# Parking_Sensor_USB_-v18.net
KiCad netlist of a schematic drawn in EAGLE
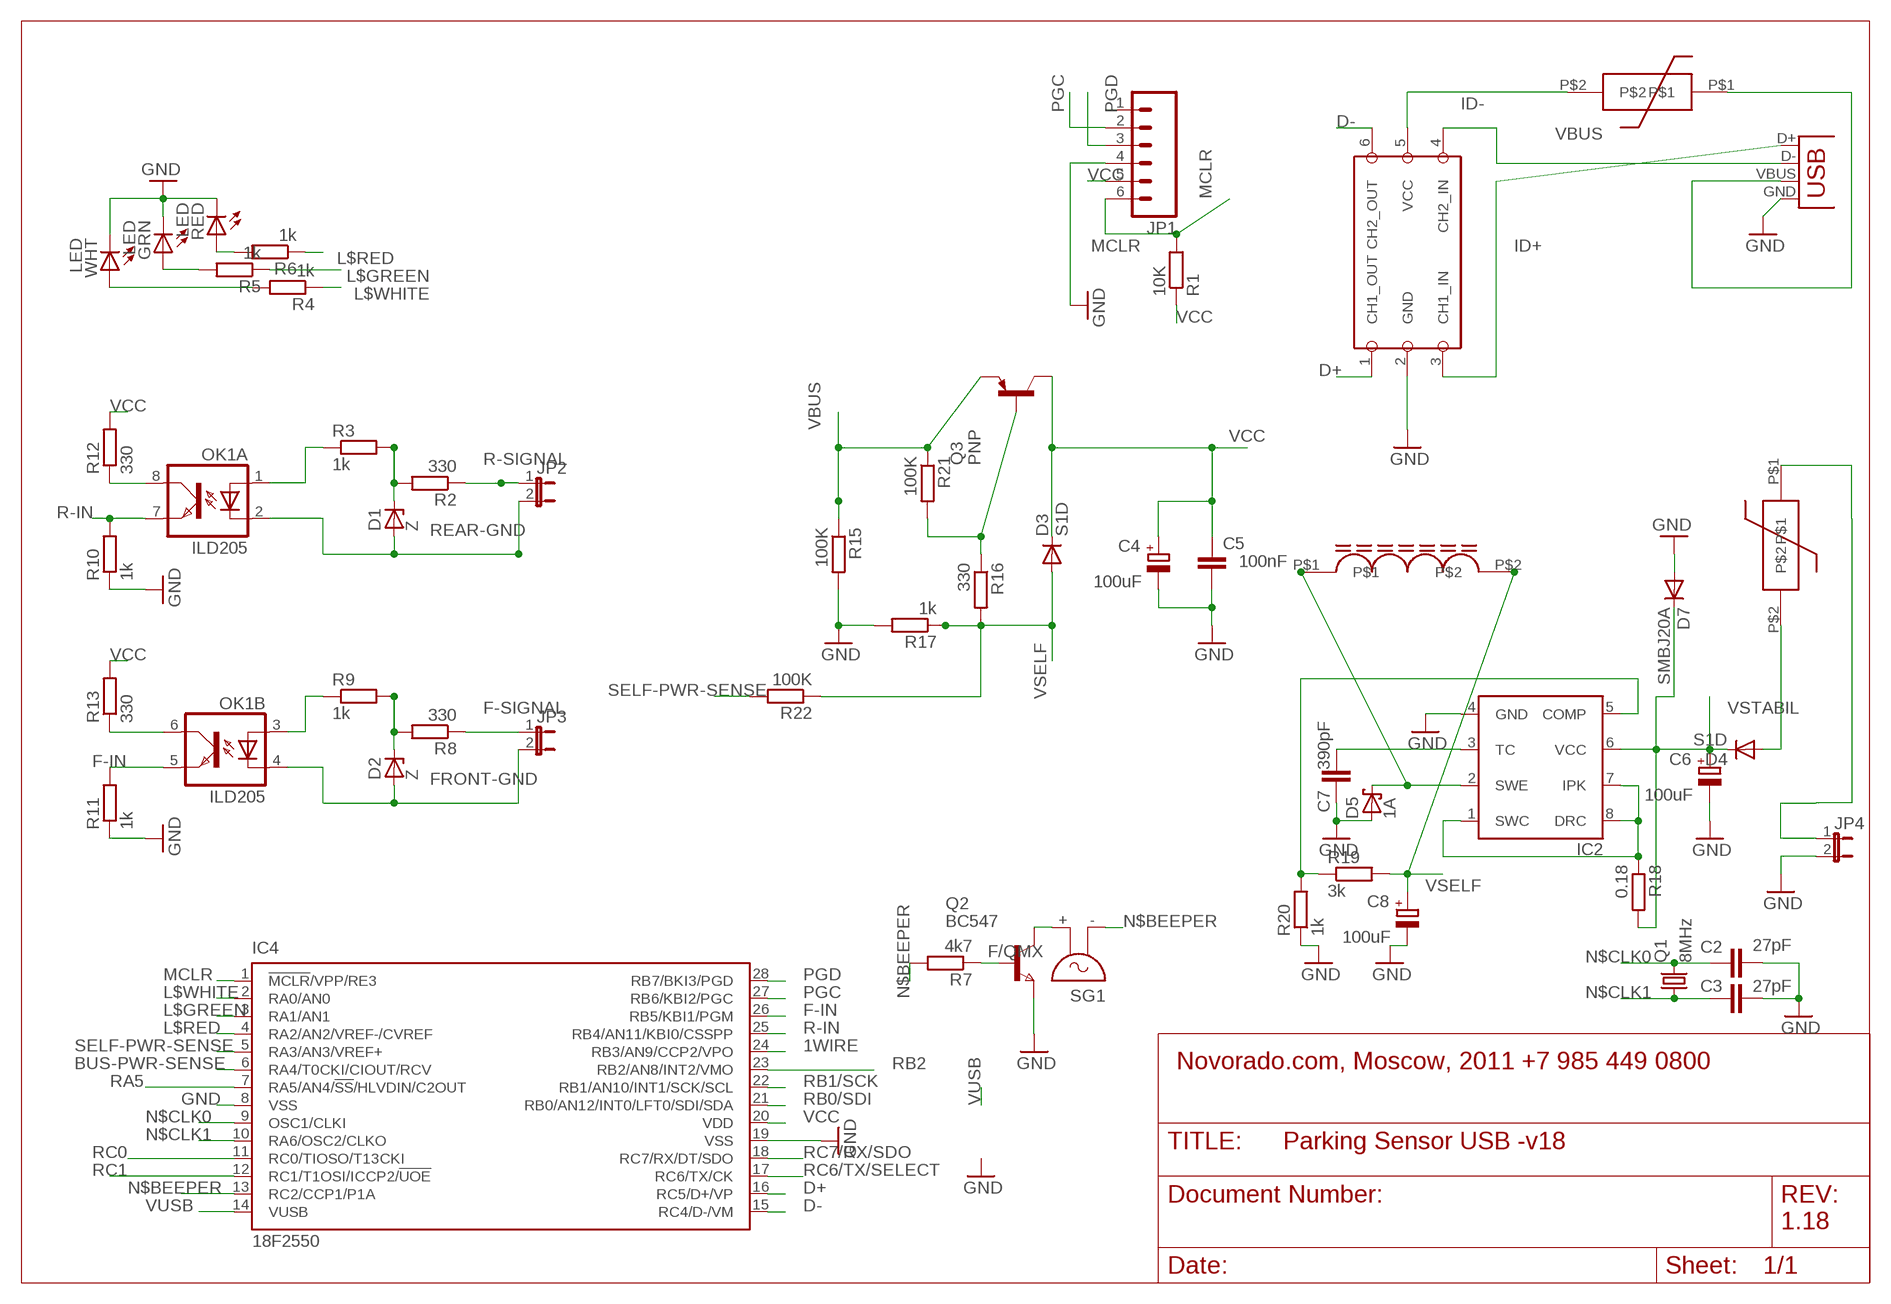
[diagram p0: schematic, sheet 1]

(export (version "E")
  (design (tool "Eeschema 10.0.6"))
  (components
    (comp (ref "C2")
      (value "27pF")
      (footprint "eagle-import:C1206")
      (libsource (lib "eagle-import") (part "C-EUC1206"))
    )
    (comp (ref "C3")
      (value "27pF")
      (footprint "eagle-import:C1206")
      (libsource (lib "eagle-import") (part "C-EUC1206"))
    )
    (comp (ref "C4")
      (value "100uF")
      (footprint "eagle-import:153CLV-0505")
      (libsource (lib "eagle-import") (part "CPOL-EU153CLV-0505"))
    )
    (comp (ref "C5")
      (value "100nF")
      (footprint "eagle-import:C0603")
      (libsource (lib "eagle-import") (part "C-EUC0603"))
    )
    (comp (ref "C6")
      (value "100uF")
      (footprint "eagle-import:153CLV-0505")
      (libsource (lib "eagle-import") (part "CPOL-EU153CLV-0505"))
    )
    (comp (ref "C7")
      (value "390pF")
      (footprint "eagle-import:C0805")
      (libsource (lib "eagle-import") (part "C-EUC0805"))
    )
    (comp (ref "C8")
      (value "100uF")
      (footprint "eagle-import:153CLV-0505")
      (libsource (lib "eagle-import") (part "CPOL-EU153CLV-0505"))
    )
    (comp (ref "D1")
      (value "Z")
      (footprint "eagle-import:SOT23")
      (libsource (lib "eagle-import") (part "ZENER-DIODESOT23"))
    )
    (comp (ref "D2")
      (value "Z")
      (footprint "eagle-import:SOT23")
      (libsource (lib "eagle-import") (part "ZENER-DIODESOT23"))
    )
    (comp (ref "D3")
      (value "S1D")
      (footprint "eagle-import:DO214AC")
      (libsource (lib "eagle-import") (part "DIODE-DO214AC"))
    )
    (comp (ref "D4")
      (value "S1D")
      (footprint "eagle-import:DO-214AC")
      (libsource (lib "eagle-import") (part "DIODE-DO-214AC"))
    )
    (comp (ref "D5")
      (value "1A")
      (footprint "eagle-import:SMB")
      (libsource (lib "eagle-import") (part "MBRS130LT3"))
    )
    (comp (ref "D7")
      (value "SMBJ20A")
      (footprint "eagle-import:DO214AA")
      (libsource (lib "eagle-import") (part "DIODE-DO214AA"))
    )
    (comp (ref "GRN")
      (value "LED")
      (footprint "eagle-import:CHIPLED_0805")
      (libsource (lib "eagle-import") (part "LEDCHIPLED_0805"))
    )
    (comp (ref "IC2")
      (value "MC34063AD")
      (footprint "eagle-import:SO08")
      (libsource (lib "eagle-import") (part "MC34063AD"))
    )
    (comp (ref "IC4")
      (value "18F2550")
      (footprint "eagle-import:SO28W")
      (fields
        (field (name "MF") "MICROCHIP")
        (field (name "MPN") "PIC18F2550-I/SO")
        (field (name "MPN_1") "PIC18F2550-I/SO")
        (field (name "OC_FARNELL") "9321268")
        (field (name "OC_NEWARK") "73K1297")
      )
      (libsource (lib "eagle-import") (part "PIC18F2_28W550"))
    )
    (comp (ref "JP1")
      (value "M06SMD")
      (footprint "eagle-import:1X06-SMD")
      (libsource (lib "eagle-import") (part "M06SMD"))
    )
    (comp (ref "JP2")
      (value "JP1E")
      (footprint "eagle-import:JP1")
      (libsource (lib "eagle-import") (part "JP1E"))
    )
    (comp (ref "JP3")
      (value "JP1E")
      (footprint "eagle-import:JP1")
      (libsource (lib "eagle-import") (part "JP1E"))
    )
    (comp (ref "JP4")
      (value "JP1E")
      (footprint "eagle-import:JP1")
      (libsource (lib "eagle-import") (part "JP1E"))
    )
    (comp (ref "OK1")
      (value "ILD205")
      (footprint "eagle-import:SOIC08")
      (fields (field (name "MF") "VISHAY/TELEFUNKEN") (field (name "MPN") "ILD205T"))
      (libsource (lib "eagle-import") (part "ILD205"))
    )
    (comp (ref "Q1")
      (value "8MHz")
      (footprint "eagle-import:HC49UP")
      (fields (field (name "OC_FARNELL") "unknown"))
      (libsource (lib "eagle-import") (part "CRYSTALHC49UP"))
    )
    (comp (ref "Q2")
      (value "BC547")
      (footprint "eagle-import:SOT-23")
      (fields (field (name "MPN") "DSS20201L-7"))
      (libsource (lib "eagle-import") (part "NPNSOT23"))
    )
    (comp (ref "Q3")
      (value "PNP")
      (footprint "eagle-import:SOT23-BEC")
      (libsource (lib "eagle-import") (part "BC807SMD-40"))
    )
    (comp (ref "R1")
      (value "10K")
      (footprint "eagle-import:M1206")
      (libsource (lib "eagle-import") (part "R-EU_M1206"))
    )
    (comp (ref "R2")
      (value "330")
      (footprint "eagle-import:M1206")
      (libsource (lib "eagle-import") (part "resistor_R-EU_M1206"))
    )
    (comp (ref "R3")
      (value "1k")
      (footprint "eagle-import:M1206")
      (libsource (lib "eagle-import") (part "resistor_R-EU_M1206"))
    )
    (comp (ref "R4")
      (value "1k")
      (footprint "eagle-import:M1206")
      (libsource (lib "eagle-import") (part "resistor_R-EU_M1206"))
    )
    (comp (ref "R5")
      (value "1k")
      (footprint "eagle-import:M1206")
      (libsource (lib "eagle-import") (part "resistor_R-EU_M1206"))
    )
    (comp (ref "R6")
      (value "1k")
      (footprint "eagle-import:M1206")
      (libsource (lib "eagle-import") (part "resistor_R-EU_M1206"))
    )
    (comp (ref "R7")
      (value "4k7")
      (footprint "eagle-import:M1206")
      (libsource (lib "eagle-import") (part "R-EU_M1206"))
    )
    (comp (ref "R8")
      (value "330")
      (footprint "eagle-import:M1206")
      (libsource (lib "eagle-import") (part "resistor_R-EU_M1206"))
    )
    (comp (ref "R9")
      (value "1k")
      (footprint "eagle-import:M1206")
      (libsource (lib "eagle-import") (part "resistor_R-EU_M1206"))
    )
    (comp (ref "R10")
      (value "1k")
      (footprint "eagle-import:M1206")
      (libsource (lib "eagle-import") (part "resistor_R-EU_M1206"))
    )
    (comp (ref "R11")
      (value "1k")
      (footprint "eagle-import:M1206")
      (libsource (lib "eagle-import") (part "resistor_R-EU_M1206"))
    )
    (comp (ref "R12")
      (value "330")
      (footprint "eagle-import:M1206")
      (libsource (lib "eagle-import") (part "resistor_R-EU_M1206"))
    )
    (comp (ref "R13")
      (value "330")
      (footprint "eagle-import:M1206")
      (libsource (lib "eagle-import") (part "resistor_R-EU_M1206"))
    )
    (comp (ref "R15")
      (value "100K")
      (footprint "eagle-import:M1206")
      (libsource (lib "eagle-import") (part "R-EU_M1206"))
    )
    (comp (ref "R16")
      (value "330")
      (footprint "eagle-import:M1206")
      (libsource (lib "eagle-import") (part "R-EU_M1206"))
    )
    (comp (ref "R17")
      (value "1k")
      (footprint "eagle-import:M1206")
      (libsource (lib "eagle-import") (part "R-EU_M1206"))
    )
    (comp (ref "R18")
      (value "0.18")
      (footprint "eagle-import:0204_7")
      (libsource (lib "eagle-import") (part "R-EU_0204/7"))
    )
    (comp (ref "R19")
      (value "3k")
      (footprint "eagle-import:M1206")
      (libsource (lib "eagle-import") (part "resistor_R-EU_M1206"))
    )
    (comp (ref "R20")
      (value "1k")
      (footprint "eagle-import:M1206")
      (libsource (lib "eagle-import") (part "resistor_R-EU_M1206"))
    )
    (comp (ref "R21")
      (value "100K")
      (footprint "eagle-import:M1206")
      (libsource (lib "eagle-import") (part "R-EU_M1206"))
    )
    (comp (ref "R22")
      (value "100K")
      (footprint "eagle-import:M1206")
      (libsource (lib "eagle-import") (part "R-EU_M1206"))
    )
    (comp (ref "RED")
      (value "LED")
      (footprint "eagle-import:CHIPLED_0805")
      (libsource (lib "eagle-import") (part "LEDCHIPLED_0805"))
    )
    (comp (ref "SG1")
      (value "F/QMX")
      (footprint "eagle-import:F_QMX")
      (libsource (lib "eagle-import") (part "F/QMX"))
    )
    (comp (ref "U$1")
      (value "EMI")
      (footprint "eagle-import:SOT23-DBV")
      (libsource (lib "eagle-import") (part "TPD2S017DBVR"))
    )
    (comp (ref "U$2")
      (value "MF-SM050")
      (footprint "eagle-import:SMD2029")
      (libsource (lib "eagle-import") (part "MF-SM050"))
    )
    (comp (ref "U$3")
      (value "MF-SM050")
      (footprint "eagle-import:SMD2029")
      (libsource (lib "eagle-import") (part "MF-SM050"))
    )
    (comp (ref "U$5")
      (value "SDR0302")
      (footprint "eagle-import:SDR0302")
      (libsource (lib "eagle-import") (part "SDR0302"))
    )
    (comp (ref "WHT")
      (value "LED")
      (footprint "eagle-import:CHIP-LED0805")
      (libsource (lib "eagle-import") (part "LEDCHIP-LED0805"))
    )
    (comp (ref "X2")
      (value "USBSMD")
      (footprint "eagle-import:USB-MINIB")
      (libsource (lib "eagle-import") (part "USBSMD"))
    )
  )
  (nets
    (net (code "1") (name "/1WIRE") (class "Default")
      (node (ref "IC4") (pin "24") (pinfunction "RB3/AN9/CCP2/VPO_24") (pintype "bidirectional"))
    )
    (net (code "2") (name "/BUS-PWR-SENSE") (class "Default")
      (node (ref "IC4") (pin "6") (pinfunction "RA4/T0CKI/CIOUT/RCV_6") (pintype "bidirectional"))
    )
    (net (code "3") (name "/D+") (class "Default")
      (node (ref "IC4") (pin "16") (pinfunction "RC5/D+/VP_16") (pintype "bidirectional"))
      (node (ref "U$1") (pin "1") (pinfunction "CH1_OUT_1") (pintype "bidirectional"))
    )
    (net (code "4") (name "/D-") (class "Default")
      (node (ref "IC4") (pin "15") (pinfunction "RC4/D-/VM_15") (pintype "bidirectional"))
      (node (ref "U$1") (pin "6") (pinfunction "CH2_OUT_6") (pintype "bidirectional"))
    )
    (net (code "5") (name "/F-IN") (class "Default")
      (node (ref "IC4") (pin "26") (pinfunction "RB5/KBI1/PGM_26") (pintype "bidirectional"))
      (node (ref "OK1") (pin "5") (pinfunction "EMIT_5") (pintype "passive"))
      (node (ref "R11") (pin "2") (pinfunction "2_2") (pintype "passive"))
    )
    (net (code "6") (name "/F-SIGNAL") (class "Default")
      (node (ref "JP3") (pin "1") (pinfunction "1_1") (pintype "passive"))
      (node (ref "R8") (pin "1") (pinfunction "1_1") (pintype "passive"))
    )
    (net (code "7") (name "/FRONT-GND") (class "Default")
      (node (ref "D2") (pin "1") (pinfunction "A_1") (pintype "passive"))
      (node (ref "JP3") (pin "2") (pinfunction "2_2") (pintype "passive"))
      (node (ref "OK1") (pin "4") (pinfunction "C_4") (pintype "passive"))
    )
    (net (code "8") (name "/ID+") (class "Default")
      (node (ref "U$1") (pin "3") (pinfunction "CH1_IN_3") (pintype "bidirectional"))
      (node (ref "X2") (pin "D+") (pinfunction "D+_D+") (pintype "bidirectional"))
    )
    (net (code "9") (name "/ID-") (class "Default")
      (node (ref "U$1") (pin "4") (pinfunction "CH2_IN_4") (pintype "bidirectional"))
      (node (ref "X2") (pin "D-") (pinfunction "D-_D-") (pintype "bidirectional"))
    )
    (net (code "10") (name "/L$GREEN") (class "Default")
      (node (ref "IC4") (pin "3") (pinfunction "RA1/AN1_3") (pintype "bidirectional"))
      (node (ref "R5") (pin "1") (pinfunction "1_1") (pintype "passive"))
    )
    (net (code "11") (name "/L$RED") (class "Default")
      (node (ref "IC4") (pin "4") (pinfunction "RA2/AN2/VREF-/CVREF_4") (pintype "bidirectional"))
      (node (ref "R6") (pin "1") (pinfunction "1_1") (pintype "passive"))
    )
    (net (code "12") (name "/L$WHITE") (class "Default")
      (node (ref "IC4") (pin "2") (pinfunction "RA0/AN0_2") (pintype "bidirectional"))
      (node (ref "R4") (pin "1") (pinfunction "1_1") (pintype "passive"))
    )
    (net (code "13") (name "/MCLR") (class "Default")
      (node (ref "IC4") (pin "1") (pinfunction "~{MCLR}/VPP/RE3_1") (pintype "input"))
      (node (ref "JP1") (pin "6") (pinfunction "6_6") (pintype "passive"))
      (node (ref "R1") (pin "2") (pinfunction "2_2") (pintype "passive"))
    )
    (net (code "14") (name "/N$BEEPER") (class "Default")
      (node (ref "IC4") (pin "13") (pinfunction "RC2/CCP1/P1A_13") (pintype "bidirectional"))
      (node (ref "R7") (pin "2") (pinfunction "2_2") (pintype "passive"))
      (node (ref "SG1") (pin "-") (pinfunction "1_-") (pintype "passive"))
    )
    (net (code "15") (name "/N$CLK0") (class "Default")
      (node (ref "C2") (pin "1") (pinfunction "1_1") (pintype "passive"))
      (node (ref "IC4") (pin "9") (pinfunction "OSC1/CLKI_9") (pintype "input"))
      (node (ref "Q1") (pin "2") (pinfunction "2_2") (pintype "passive"))
    )
    (net (code "16") (name "/N$CLK1") (class "Default")
      (node (ref "C3") (pin "1") (pinfunction "1_1") (pintype "passive"))
      (node (ref "IC4") (pin "10") (pinfunction "RA6/OSC2/CLKO_10") (pintype "output"))
      (node (ref "Q1") (pin "1") (pinfunction "1_1") (pintype "passive"))
    )
    (net (code "17") (name "/PGC") (class "Default")
      (node (ref "IC4") (pin "27") (pinfunction "RB6/KBI2/PGC_27") (pintype "bidirectional"))
      (node (ref "JP1") (pin "2") (pinfunction "2_2") (pintype "passive"))
    )
    (net (code "18") (name "/PGD") (class "Default")
      (node (ref "IC4") (pin "28") (pinfunction "RB7/BKI3/PGD_28") (pintype "bidirectional"))
      (node (ref "JP1") (pin "3") (pinfunction "3_3") (pintype "passive"))
    )
    (net (code "19") (name "/R-IN") (class "Default")
      (node (ref "IC4") (pin "25") (pinfunction "RB4/AN11/KBI0/CSSPP_25") (pintype "bidirectional"))
      (node (ref "OK1") (pin "7") (pinfunction "EMIT_7") (pintype "passive"))
      (node (ref "R10") (pin "2") (pinfunction "2_2") (pintype "passive"))
    )
    (net (code "20") (name "/R-SIGNAL") (class "Default")
      (node (ref "JP2") (pin "1") (pinfunction "1_1") (pintype "passive"))
      (node (ref "R2") (pin "1") (pinfunction "1_1") (pintype "passive"))
    )
    (net (code "21") (name "/RA5") (class "Default")
      (node (ref "IC4") (pin "7") (pinfunction "RA5/AN4/~{SS}/HLVDIN/C2OUT_7") (pintype "bidirectional"))
    )
    (net (code "22") (name "/RB0{slash}SDI") (class "Default")
      (node (ref "IC4") (pin "21") (pinfunction "RB0/AN12/INT0/LFT0/SDI/SDA_21") (pintype "bidirectional"))
    )
    (net (code "23") (name "/RB1{slash}SCK") (class "Default")
      (node (ref "IC4") (pin "22") (pinfunction "RB1/AN10/INT1/SCK/SCL_22") (pintype "bidirectional"))
    )
    (net (code "24") (name "/RB2") (class "Default")
      (node (ref "IC4") (pin "23") (pinfunction "RB2/AN8/INT2/VMO_23") (pintype "bidirectional"))
    )
    (net (code "25") (name "/RC0") (class "Default")
      (node (ref "IC4") (pin "11") (pinfunction "RC0/TIOSO/T13CKI_11") (pintype "bidirectional"))
    )
    (net (code "26") (name "/RC1") (class "Default")
      (node (ref "IC4") (pin "12") (pinfunction "RC1/T1OSI/ICCP2/~{UOE}_12") (pintype "bidirectional"))
    )
    (net (code "27") (name "/RC6{slash}TX{slash}SELECT") (class "Default")
      (node (ref "IC4") (pin "17") (pinfunction "RC6/TX/CK_17") (pintype "bidirectional"))
    )
    (net (code "28") (name "/RC7{slash}RX{slash}SDO") (class "Default")
      (node (ref "IC4") (pin "18") (pinfunction "RC7/RX/DT/SDO_18") (pintype "bidirectional"))
    )
    (net (code "29") (name "/REAR-GND") (class "Default")
      (node (ref "D1") (pin "1") (pinfunction "A_1") (pintype "passive"))
      (node (ref "JP2") (pin "2") (pinfunction "2_2") (pintype "passive"))
      (node (ref "OK1") (pin "2") (pinfunction "C_2") (pintype "passive"))
    )
    (net (code "30") (name "/SELF-PWR-SENSE") (class "Default")
      (node (ref "IC4") (pin "5") (pinfunction "RA3/AN3/VREF+_5") (pintype "bidirectional"))
      (node (ref "R22") (pin "2") (pinfunction "2_2") (pintype "passive"))
    )
    (net (code "31") (name "/VBUS") (class "Default")
      (node (ref "Q3") (pin "E") (pinfunction "E_E") (pintype "passive"))
      (node (ref "R15") (pin "1") (pinfunction "1_1") (pintype "passive"))
      (node (ref "R21") (pin "1") (pinfunction "1_1") (pintype "passive"))
      (node (ref "U$1") (pin "5") (pinfunction "VCC_5") (pintype "bidirectional"))
      (node (ref "U$2") (pin "P$2") (pinfunction "P$2_P$2") (pintype "bidirectional"))
    )
    (net (code "32") (name "/VCC") (class "Default")
      (node (ref "C4") (pin "+") (pinfunction "+_+") (pintype "passive"))
      (node (ref "C5") (pin "1") (pinfunction "1_1") (pintype "passive"))
      (node (ref "D3") (pin "C") (pinfunction "C_C") (pintype "passive"))
      (node (ref "IC4") (pin "20") (pinfunction "VDD_20") (pintype "power_in"))
      (node (ref "JP1") (pin "5") (pinfunction "5_5") (pintype "passive"))
      (node (ref "Q3") (pin "C") (pinfunction "C_C") (pintype "passive"))
      (node (ref "R1") (pin "1") (pinfunction "1_1") (pintype "passive"))
      (node (ref "R12") (pin "2") (pinfunction "2_2") (pintype "passive"))
      (node (ref "R13") (pin "2") (pinfunction "2_2") (pintype "passive"))
    )
    (net (code "33") (name "/VSELF") (class "Default")
      (node (ref "C8") (pin "+") (pinfunction "+_+") (pintype "passive"))
      (node (ref "D3") (pin "A") (pinfunction "A_A") (pintype "passive"))
      (node (ref "R16") (pin "2") (pinfunction "2_2") (pintype "passive"))
      (node (ref "R17") (pin "1") (pinfunction "1_1") (pintype "passive"))
      (node (ref "R19") (pin "2") (pinfunction "2_2") (pintype "passive"))
      (node (ref "R22") (pin "1") (pinfunction "1_1") (pintype "passive"))
      (node (ref "U$5") (pin "P$2") (pinfunction "P$2_P$2") (pintype "bidirectional"))
    )
    (net (code "34") (name "/VSTABIL") (class "Default")
      (node (ref "C6") (pin "+") (pinfunction "+_+") (pintype "passive"))
      (node (ref "D4") (pin "C") (pinfunction "C_C") (pintype "passive"))
      (node (ref "D7") (pin "C") (pinfunction "C_C") (pintype "passive"))
      (node (ref "IC2") (pin "6") (pinfunction "VCC_6") (pintype "power_in"))
      (node (ref "R18") (pin "2") (pinfunction "2_2") (pintype "passive"))
    )
    (net (code "35") (name "/VUSB") (class "Default")
      (node (ref "IC4") (pin "14") (pinfunction "VUSB_14") (pintype "bidirectional"))
    )
    (net (code "36") (name "GND") (class "Default")
      (node (ref "C2") (pin "2") (pinfunction "2_2") (pintype "passive"))
      (node (ref "C3") (pin "2") (pinfunction "2_2") (pintype "passive"))
      (node (ref "C4") (pin "-") (pinfunction "-_-") (pintype "passive"))
      (node (ref "C5") (pin "2") (pinfunction "2_2") (pintype "passive"))
      (node (ref "C6") (pin "-") (pinfunction "-_-") (pintype "passive"))
      (node (ref "C7") (pin "1") (pinfunction "1_1") (pintype "passive"))
      (node (ref "C8") (pin "-") (pinfunction "-_-") (pintype "passive"))
      (node (ref "D5") (pin "A") (pinfunction "A_A") (pintype "passive"))
      (node (ref "D7") (pin "A") (pinfunction "A_A") (pintype "passive"))
      (node (ref "GRN") (pin "C") (pinfunction "C_C") (pintype "passive"))
      (node (ref "IC2") (pin "4") (pinfunction "GND_4") (pintype "power_in"))
      (node (ref "IC4") (pin "19") (pinfunction "VSS_19") (pintype "power_in"))
      (node (ref "IC4") (pin "8") (pinfunction "VSS_8") (pintype "power_in"))
      (node (ref "JP1") (pin "4") (pinfunction "4_4") (pintype "passive"))
      (node (ref "JP4") (pin "2") (pinfunction "2_2") (pintype "passive"))
      (node (ref "Q2") (pin "2") (pinfunction "E_2") (pintype "passive"))
      (node (ref "R10") (pin "1") (pinfunction "1_1") (pintype "passive"))
      (node (ref "R11") (pin "1") (pinfunction "1_1") (pintype "passive"))
      (node (ref "R15") (pin "2") (pinfunction "2_2") (pintype "passive"))
      (node (ref "R17") (pin "2") (pinfunction "2_2") (pintype "passive"))
      (node (ref "R20") (pin "1") (pinfunction "1_1") (pintype "passive"))
      (node (ref "RED") (pin "C") (pinfunction "C_C") (pintype "passive"))
      (node (ref "U$1") (pin "2") (pinfunction "GND_2") (pintype "bidirectional"))
      (node (ref "WHT") (pin "C") (pinfunction "C_C") (pintype "passive"))
      (node (ref "X2") (pin "GND") (pinfunction "GND_GND") (pintype "bidirectional"))
    )
    (net (code "37") (name "Net-(D1-C)") (class "Default")
      (node (ref "D1") (pin "3") (pinfunction "C_3") (pintype "passive"))
      (node (ref "R2") (pin "2") (pinfunction "2_2") (pintype "passive"))
      (node (ref "R3") (pin "2") (pinfunction "2_2") (pintype "passive"))
    )
    (net (code "38") (name "Net-(D2-C)") (class "Default")
      (node (ref "D2") (pin "3") (pinfunction "C_3") (pintype "passive"))
      (node (ref "R8") (pin "2") (pinfunction "2_2") (pintype "passive"))
      (node (ref "R9") (pin "2") (pinfunction "2_2") (pintype "passive"))
    )
    (net (code "39") (name "Net-(D4-PadA)") (class "Default")
      (node (ref "D4") (pin "A") (pinfunction "A_A") (pintype "passive"))
      (node (ref "U$3") (pin "P$2") (pinfunction "P$2_P$2") (pintype "bidirectional"))
    )
    (net (code "40") (name "Net-(GRN-PadA)") (class "Default")
      (node (ref "GRN") (pin "A") (pinfunction "A_A") (pintype "passive"))
      (node (ref "R5") (pin "2") (pinfunction "2_2") (pintype "passive"))
    )
    (net (code "41") (name "Net-(IC2-COMP)") (class "Default")
      (node (ref "IC2") (pin "5") (pinfunction "COMP_5") (pintype "input"))
      (node (ref "R19") (pin "1") (pinfunction "1_1") (pintype "passive"))
      (node (ref "R20") (pin "2") (pinfunction "2_2") (pintype "passive"))
    )
    (net (code "42") (name "Net-(IC2-DRC)") (class "Default")
      (node (ref "IC2") (pin "1") (pinfunction "SWC_1") (pintype "bidirectional"))
      (node (ref "IC2") (pin "7") (pinfunction "IPK_7") (pintype "input"))
      (node (ref "IC2") (pin "8") (pinfunction "DRC_8") (pintype "input"))
      (node (ref "R18") (pin "1") (pinfunction "1_1") (pintype "passive"))
    )
    (net (code "43") (name "Net-(IC2-SWE)") (class "Default")
      (node (ref "D5") (pin "C") (pinfunction "C_C") (pintype "passive"))
      (node (ref "IC2") (pin "2") (pinfunction "SWE_2") (pintype "bidirectional"))
      (node (ref "U$5") (pin "P$1") (pinfunction "P$1_P$1") (pintype "bidirectional"))
    )
    (net (code "44") (name "Net-(IC2-TC)") (class "Default")
      (node (ref "C7") (pin "2") (pinfunction "2_2") (pintype "passive"))
      (node (ref "IC2") (pin "3") (pinfunction "TC_3") (pintype "passive"))
    )
    (net (code "45") (name "Net-(JP4-Pad1)") (class "Default")
      (node (ref "JP4") (pin "1") (pinfunction "1_1") (pintype "passive"))
      (node (ref "U$3") (pin "P$1") (pinfunction "P$1_P$1") (pintype "bidirectional"))
    )
    (net (code "46") (name "Net-(OK1A-A)") (class "Default")
      (node (ref "OK1") (pin "1") (pinfunction "A_1") (pintype "passive"))
      (node (ref "R3") (pin "1") (pinfunction "1_1") (pintype "passive"))
    )
    (net (code "47") (name "Net-(OK1A-COL)") (class "Default")
      (node (ref "OK1") (pin "8") (pinfunction "COL_8") (pintype "passive"))
      (node (ref "R12") (pin "1") (pinfunction "1_1") (pintype "passive"))
    )
    (net (code "48") (name "Net-(OK1B-A)") (class "Default")
      (node (ref "OK1") (pin "3") (pinfunction "A_3") (pintype "passive"))
      (node (ref "R9") (pin "1") (pinfunction "1_1") (pintype "passive"))
    )
    (net (code "49") (name "Net-(OK1B-COL)") (class "Default")
      (node (ref "OK1") (pin "6") (pinfunction "COL_6") (pintype "passive"))
      (node (ref "R13") (pin "1") (pinfunction "1_1") (pintype "passive"))
    )
    (net (code "50") (name "Net-(Q2-B)") (class "Default")
      (node (ref "Q2") (pin "3") (pinfunction "B_3") (pintype "passive"))
      (node (ref "R7") (pin "1") (pinfunction "1_1") (pintype "passive"))
    )
    (net (code "51") (name "Net-(Q2-C)") (class "Default")
      (node (ref "Q2") (pin "1") (pinfunction "C_1") (pintype "passive"))
      (node (ref "SG1") (pin "+") (pinfunction "2_+") (pintype "passive"))
    )
    (net (code "52") (name "Net-(Q3-PadB)") (class "Default")
      (node (ref "Q3") (pin "B") (pinfunction "B_B") (pintype "passive"))
      (node (ref "R16") (pin "1") (pinfunction "1_1") (pintype "passive"))
      (node (ref "R21") (pin "2") (pinfunction "2_2") (pintype "passive"))
    )
    (net (code "53") (name "Net-(R4-Pad2)") (class "Default")
      (node (ref "R4") (pin "2") (pinfunction "2_2") (pintype "passive"))
      (node (ref "WHT") (pin "A") (pinfunction "A_A") (pintype "passive"))
    )
    (net (code "54") (name "Net-(R6-Pad2)") (class "Default")
      (node (ref "R6") (pin "2") (pinfunction "2_2") (pintype "passive"))
      (node (ref "RED") (pin "A") (pinfunction "A_A") (pintype "passive"))
    )
    (net (code "55") (name "Net-(U$2-PadP$1)") (class "Default")
      (node (ref "U$2") (pin "P$1") (pinfunction "P$1_P$1") (pintype "bidirectional"))
      (node (ref "X2") (pin "VBUS") (pinfunction "VBUS_VBUS") (pintype "bidirectional"))
    )
    (net (code "56") (name "unconnected-(JP1-Pad1)") (class "Default")
      (node (ref "JP1") (pin "1") (pinfunction "1_1") (pintype "passive"))
    )
  )
)
